# RasPi-BplusHAT.net
KiCad netlist of a schematic drawn in EAGLE
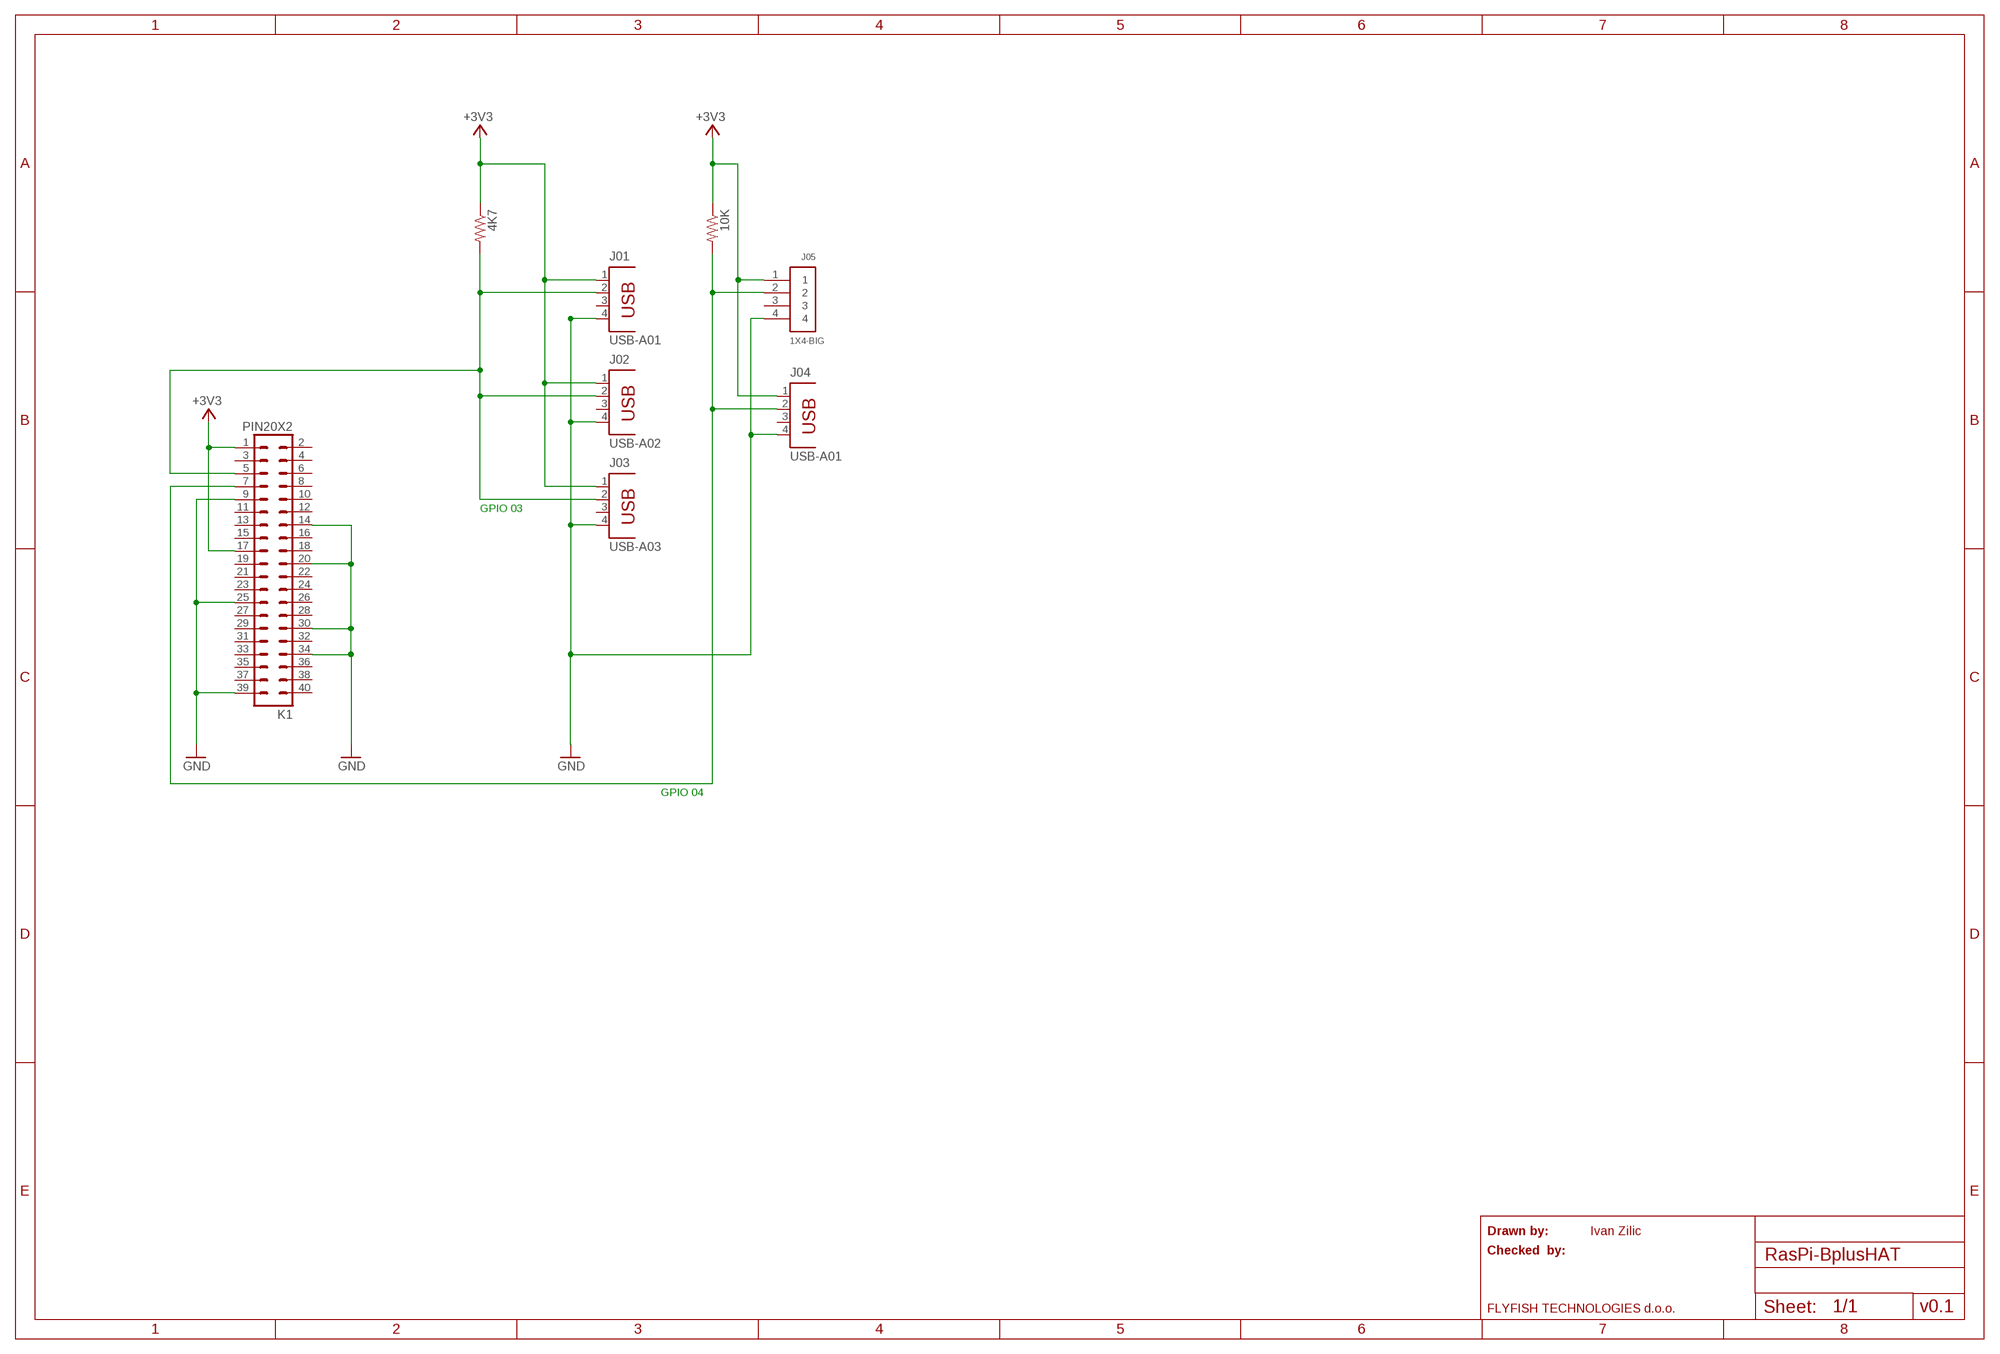
[diagram p0: schematic, sheet 1]

(export (version "E")
  (design (tool "Eeschema 10.0.6"))
  (components
    (comp (ref "4K7")
      (value "R-US_0204/7")
      (footprint "eagle-import:0204_7")
      (libsource (lib "eagle-import") (part "R-US_0204/7"))
    )
    (comp (ref "10K")
      (value "R-US_0204/7")
      (footprint "eagle-import:0204_7")
      (libsource (lib "eagle-import") (part "R-US_0204/7"))
    )
    (comp (ref "J01")
      (value "USB-A01")
      (footprint "eagle-import:PN87520")
      (libsource (lib "eagle-import") (part "PN87520"))
    )
    (comp (ref "J02")
      (value "USB-A02")
      (footprint "eagle-import:PN87520")
      (libsource (lib "eagle-import") (part "PN87520"))
    )
    (comp (ref "J03")
      (value "USB-A03")
      (footprint "eagle-import:PN87520")
      (libsource (lib "eagle-import") (part "PN87520"))
    )
    (comp (ref "J04")
      (value "USB-A01")
      (footprint "eagle-import:PN87520")
      (libsource (lib "eagle-import") (part "PN87520"))
    )
    (comp (ref "J05")
      (value "1X4-BIG")
      (footprint "eagle-import:1X04-BIG")
      (libsource (lib "eagle-import") (part "1X4-BIG"))
    )
    (comp (ref "K1")
      (value "PIN20X2")
      (footprint "eagle-import:PIN_20X2")
      (libsource (lib "eagle-import") (part "PIN20X2"))
    )
  )
  (nets
    (net (code "1") (name "+3V3") (class "Default")
      (node (ref "10K") (pin "1") (pinfunction "1_1") (pintype "passive"))
      (node (ref "4K7") (pin "1") (pinfunction "1_1") (pintype "passive"))
      (node (ref "J01") (pin "1") (pinfunction "1_1") (pintype "passive"))
      (node (ref "J02") (pin "1") (pinfunction "1_1") (pintype "passive"))
      (node (ref "J03") (pin "1") (pinfunction "1_1") (pintype "passive"))
      (node (ref "J04") (pin "1") (pinfunction "1_1") (pintype "passive"))
      (node (ref "J05") (pin "1") (pinfunction "1_1") (pintype "bidirectional"))
      (node (ref "K1") (pin "1") (pinfunction "1_1") (pintype "passive"))
      (node (ref "K1") (pin "17") (pinfunction "17_17") (pintype "passive"))
    )
    (net (code "2") (name "GND") (class "Default")
      (node (ref "J01") (pin "4") (pinfunction "4_4") (pintype "passive"))
      (node (ref "J02") (pin "4") (pinfunction "4_4") (pintype "passive"))
      (node (ref "J03") (pin "4") (pinfunction "4_4") (pintype "passive"))
      (node (ref "J04") (pin "4") (pinfunction "4_4") (pintype "passive"))
      (node (ref "J05") (pin "4") (pinfunction "4_4") (pintype "bidirectional"))
      (node (ref "K1") (pin "14") (pinfunction "14_14") (pintype "passive"))
      (node (ref "K1") (pin "20") (pinfunction "20_20") (pintype "passive"))
      (node (ref "K1") (pin "25") (pinfunction "25_25") (pintype "passive"))
      (node (ref "K1") (pin "30") (pinfunction "30_30") (pintype "passive"))
      (node (ref "K1") (pin "34") (pinfunction "34_34") (pintype "passive"))
      (node (ref "K1") (pin "39") (pinfunction "39_39") (pintype "passive"))
      (node (ref "K1") (pin "9") (pinfunction "9_9") (pintype "passive"))
    )
    (net (code "3") (name "Net-(4K7-Pad2)") (class "Default")
      (node (ref "4K7") (pin "2") (pinfunction "2_2") (pintype "passive"))
      (node (ref "J01") (pin "2") (pinfunction "2_2") (pintype "passive"))
      (node (ref "J02") (pin "2") (pinfunction "2_2") (pintype "passive"))
      (node (ref "J03") (pin "2") (pinfunction "2_2") (pintype "passive"))
      (node (ref "K1") (pin "5") (pinfunction "5_5") (pintype "passive"))
    )
    (net (code "4") (name "Net-(10K-Pad2)") (class "Default")
      (node (ref "10K") (pin "2") (pinfunction "2_2") (pintype "passive"))
      (node (ref "J04") (pin "2") (pinfunction "2_2") (pintype "passive"))
      (node (ref "J05") (pin "2") (pinfunction "2_2") (pintype "bidirectional"))
      (node (ref "K1") (pin "7") (pinfunction "7_7") (pintype "passive"))
    )
    (net (code "5") (name "unconnected-(J01-Pad3)") (class "Default")
      (node (ref "J01") (pin "3") (pinfunction "3_3") (pintype "passive"))
    )
    (net (code "6") (name "unconnected-(J02-Pad3)") (class "Default")
      (node (ref "J02") (pin "3") (pinfunction "3_3") (pintype "passive"))
    )
    (net (code "7") (name "unconnected-(J03-Pad3)") (class "Default")
      (node (ref "J03") (pin "3") (pinfunction "3_3") (pintype "passive"))
    )
    (net (code "8") (name "unconnected-(J04-Pad3)") (class "Default")
      (node (ref "J04") (pin "3") (pinfunction "3_3") (pintype "passive"))
    )
    (net (code "9") (name "unconnected-(J05-Pad3)") (class "Default")
      (node (ref "J05") (pin "3") (pinfunction "3_3") (pintype "bidirectional"))
    )
    (net (code "10") (name "unconnected-(K1-Pad2)") (class "Default")
      (node (ref "K1") (pin "2") (pinfunction "2_2") (pintype "passive"))
    )
    (net (code "11") (name "unconnected-(K1-Pad3)") (class "Default")
      (node (ref "K1") (pin "3") (pinfunction "3_3") (pintype "passive"))
    )
    (net (code "12") (name "unconnected-(K1-Pad4)") (class "Default")
      (node (ref "K1") (pin "4") (pinfunction "4_4") (pintype "passive"))
    )
    (net (code "13") (name "unconnected-(K1-Pad6)") (class "Default")
      (node (ref "K1") (pin "6") (pinfunction "6_6") (pintype "passive"))
    )
    (net (code "14") (name "unconnected-(K1-Pad8)") (class "Default")
      (node (ref "K1") (pin "8") (pinfunction "8_8") (pintype "passive"))
    )
    (net (code "15") (name "unconnected-(K1-Pad10)") (class "Default")
      (node (ref "K1") (pin "10") (pinfunction "10_10") (pintype "passive"))
    )
    (net (code "16") (name "unconnected-(K1-Pad11)") (class "Default")
      (node (ref "K1") (pin "11") (pinfunction "11_11") (pintype "passive"))
    )
    (net (code "17") (name "unconnected-(K1-Pad12)") (class "Default")
      (node (ref "K1") (pin "12") (pinfunction "12_12") (pintype "passive"))
    )
    (net (code "18") (name "unconnected-(K1-Pad13)") (class "Default")
      (node (ref "K1") (pin "13") (pinfunction "13_13") (pintype "passive"))
    )
    (net (code "19") (name "unconnected-(K1-Pad15)") (class "Default")
      (node (ref "K1") (pin "15") (pinfunction "15_15") (pintype "passive"))
    )
    (net (code "20") (name "unconnected-(K1-Pad16)") (class "Default")
      (node (ref "K1") (pin "16") (pinfunction "16_16") (pintype "passive"))
    )
    (net (code "21") (name "unconnected-(K1-Pad18)") (class "Default")
      (node (ref "K1") (pin "18") (pinfunction "18_18") (pintype "passive"))
    )
    (net (code "22") (name "unconnected-(K1-Pad19)") (class "Default")
      (node (ref "K1") (pin "19") (pinfunction "19_19") (pintype "passive"))
    )
    (net (code "23") (name "unconnected-(K1-Pad21)") (class "Default")
      (node (ref "K1") (pin "21") (pinfunction "21_21") (pintype "passive"))
    )
    (net (code "24") (name "unconnected-(K1-Pad22)") (class "Default")
      (node (ref "K1") (pin "22") (pinfunction "22_22") (pintype "passive"))
    )
    (net (code "25") (name "unconnected-(K1-Pad23)") (class "Default")
      (node (ref "K1") (pin "23") (pinfunction "23_23") (pintype "passive"))
    )
    (net (code "26") (name "unconnected-(K1-Pad24)") (class "Default")
      (node (ref "K1") (pin "24") (pinfunction "24_24") (pintype "passive"))
    )
    (net (code "27") (name "unconnected-(K1-Pad26)") (class "Default")
      (node (ref "K1") (pin "26") (pinfunction "26_26") (pintype "passive"))
    )
    (net (code "28") (name "unconnected-(K1-Pad27)") (class "Default")
      (node (ref "K1") (pin "27") (pinfunction "27_27") (pintype "passive"))
    )
    (net (code "29") (name "unconnected-(K1-Pad28)") (class "Default")
      (node (ref "K1") (pin "28") (pinfunction "28_28") (pintype "passive"))
    )
    (net (code "30") (name "unconnected-(K1-Pad29)") (class "Default")
      (node (ref "K1") (pin "29") (pinfunction "29_29") (pintype "passive"))
    )
    (net (code "31") (name "unconnected-(K1-Pad31)") (class "Default")
      (node (ref "K1") (pin "31") (pinfunction "31_31") (pintype "passive"))
    )
    (net (code "32") (name "unconnected-(K1-Pad32)") (class "Default")
      (node (ref "K1") (pin "32") (pinfunction "32_32") (pintype "passive"))
    )
    (net (code "33") (name "unconnected-(K1-Pad33)") (class "Default")
      (node (ref "K1") (pin "33") (pinfunction "33_33") (pintype "passive"))
    )
    (net (code "34") (name "unconnected-(K1-Pad35)") (class "Default")
      (node (ref "K1") (pin "35") (pinfunction "35_35") (pintype "passive"))
    )
    (net (code "35") (name "unconnected-(K1-Pad36)") (class "Default")
      (node (ref "K1") (pin "36") (pinfunction "36_36") (pintype "passive"))
    )
    (net (code "36") (name "unconnected-(K1-Pad37)") (class "Default")
      (node (ref "K1") (pin "37") (pinfunction "37_37") (pintype "passive"))
    )
    (net (code "37") (name "unconnected-(K1-Pad38)") (class "Default")
      (node (ref "K1") (pin "38") (pinfunction "38_38") (pintype "passive"))
    )
    (net (code "38") (name "unconnected-(K1-Pad40)") (class "Default")
      (node (ref "K1") (pin "40") (pinfunction "40_40") (pintype "passive"))
    )
  )
)
